# ArduinoProMicroKame.net
KiCad netlist of a schematic drawn in EAGLE
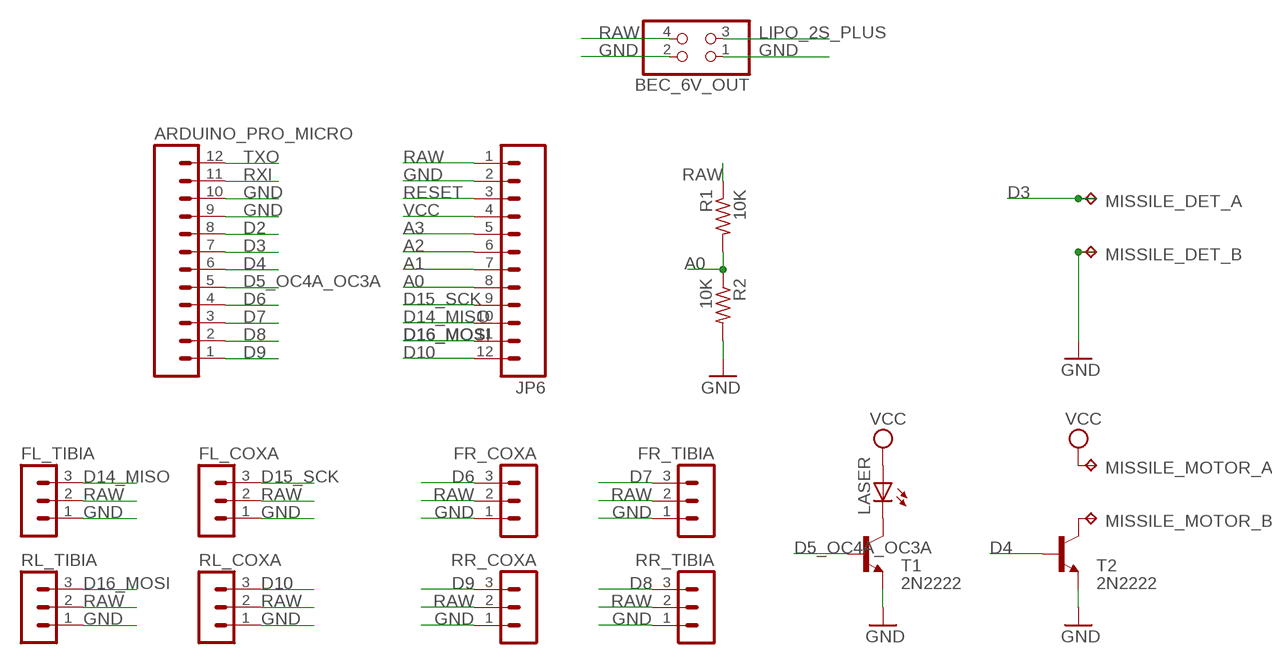
[diagram p0: schematic, sheet 1]

(export (version "E")
  (design (tool "Eeschema 10.0.6"))
  (components
    (comp (ref "ARDUINO_PRO_MICRO")
      (value "M12PTH")
      (footprint "eagle-import:1X12")
      (libsource (lib "eagle-import") (part "M12PTH"))
    )
    (comp (ref "BEC_6V_OUT")
      (value "PINHD-2X2")
      (footprint "eagle-import:2X02")
      (libsource (lib "eagle-import") (part "PINHD-2X2"))
    )
    (comp (ref "FL_COXA")
      (value "MA03-1")
      (footprint "eagle-import:MA03-1")
      (libsource (lib "eagle-import") (part "MA03-1"))
    )
    (comp (ref "FL_TIBIA")
      (value "MA03-1")
      (footprint "eagle-import:MA03-1")
      (libsource (lib "eagle-import") (part "MA03-1"))
    )
    (comp (ref "FR_COXA")
      (value "MA03-1")
      (footprint "eagle-import:MA03-1")
      (libsource (lib "eagle-import") (part "MA03-1"))
    )
    (comp (ref "FR_TIBIA")
      (value "MA03-1")
      (footprint "eagle-import:MA03-1")
      (libsource (lib "eagle-import") (part "MA03-1"))
    )
    (comp (ref "JP6")
      (value "M12PTH")
      (footprint "eagle-import:1X12")
      (libsource (lib "eagle-import") (part "M12PTH"))
    )
    (comp (ref "LASER")
      (value "LED")
      (footprint "eagle-import:SMARTLED-TTW")
      (libsource (lib "eagle-import") (part "LED"))
    )
    (comp (ref "MISSILE_DET_")
      (value "TP2P2-38-20")
      (footprint "eagle-import:P2-38-20")
      (libsource (lib "eagle-import") (part "TP2P2-38-20"))
    )
    (comp (ref "MISSILE_MOTOR_")
      (value "TP2P2-38-20")
      (footprint "eagle-import:P2-38-20")
      (libsource (lib "eagle-import") (part "TP2P2-38-20"))
    )
    (comp (ref "R1")
      (value "10K")
      (footprint "eagle-import:R2010")
      (libsource (lib "eagle-import") (part "R-US_R2010"))
    )
    (comp (ref "R2")
      (value "10K")
      (footprint "eagle-import:R2010")
      (libsource (lib "eagle-import") (part "R-US_R2010"))
    )
    (comp (ref "RL_COXA")
      (value "MA03-1")
      (footprint "eagle-import:MA03-1")
      (libsource (lib "eagle-import") (part "MA03-1"))
    )
    (comp (ref "RL_TIBIA")
      (value "MA03-1")
      (footprint "eagle-import:MA03-1")
      (libsource (lib "eagle-import") (part "MA03-1"))
    )
    (comp (ref "RR_COXA")
      (value "MA03-1")
      (footprint "eagle-import:MA03-1")
      (libsource (lib "eagle-import") (part "MA03-1"))
    )
    (comp (ref "RR_TIBIA")
      (value "MA03-1")
      (footprint "eagle-import:MA03-1")
      (libsource (lib "eagle-import") (part "MA03-1"))
    )
    (comp (ref "T1")
      (value "2N2222")
      (footprint "eagle-import:TO18")
      (libsource (lib "eagle-import") (part "2N2222"))
    )
    (comp (ref "T2")
      (value "2N2222")
      (footprint "eagle-import:TO18")
      (libsource (lib "eagle-import") (part "2N2222"))
    )
  )
  (nets
    (net (code "1") (name "/A0") (class "Default")
      (node (ref "JP6") (pin "8") (pinfunction "8_8") (pintype "passive"))
      (node (ref "R1") (pin "2") (pinfunction "2_2") (pintype "passive"))
      (node (ref "R2") (pin "1") (pinfunction "1_1") (pintype "passive"))
    )
    (net (code "2") (name "/A1") (class "Default")
      (node (ref "JP6") (pin "7") (pinfunction "7_7") (pintype "passive"))
    )
    (net (code "3") (name "/A2") (class "Default")
      (node (ref "JP6") (pin "6") (pinfunction "6_6") (pintype "passive"))
    )
    (net (code "4") (name "/A3") (class "Default")
      (node (ref "JP6") (pin "5") (pinfunction "5_5") (pintype "passive"))
    )
    (net (code "5") (name "/D2") (class "Default")
      (node (ref "ARDUINO_PRO_MICRO") (pin "8") (pinfunction "8_8") (pintype "passive"))
    )
    (net (code "6") (name "/D3") (class "Default")
      (node (ref "ARDUINO_PRO_MICRO") (pin "7") (pinfunction "7_7") (pintype "passive"))
      (node (ref "MISSILE_DET_") (pin "TP-1") (pinfunction "TP_TP-1") (pintype "input"))
    )
    (net (code "7") (name "/D4") (class "Default")
      (node (ref "ARDUINO_PRO_MICRO") (pin "6") (pinfunction "6_6") (pintype "passive"))
      (node (ref "T2") (pin "2") (pinfunction "B_2") (pintype "passive"))
    )
    (net (code "8") (name "/D5_OC4A_OC3A") (class "Default")
      (node (ref "ARDUINO_PRO_MICRO") (pin "5") (pinfunction "5_5") (pintype "passive"))
      (node (ref "T1") (pin "2") (pinfunction "B_2") (pintype "passive"))
    )
    (net (code "9") (name "/D6") (class "Default")
      (node (ref "ARDUINO_PRO_MICRO") (pin "4") (pinfunction "4_4") (pintype "passive"))
      (node (ref "FR_COXA") (pin "3") (pinfunction "3_3") (pintype "passive"))
    )
    (net (code "10") (name "/D7") (class "Default")
      (node (ref "ARDUINO_PRO_MICRO") (pin "3") (pinfunction "3_3") (pintype "passive"))
      (node (ref "FR_TIBIA") (pin "3") (pinfunction "3_3") (pintype "passive"))
    )
    (net (code "11") (name "/D8") (class "Default")
      (node (ref "ARDUINO_PRO_MICRO") (pin "2") (pinfunction "2_2") (pintype "passive"))
      (node (ref "RR_TIBIA") (pin "3") (pinfunction "3_3") (pintype "passive"))
    )
    (net (code "12") (name "/D9") (class "Default")
      (node (ref "ARDUINO_PRO_MICRO") (pin "1") (pinfunction "1_1") (pintype "passive"))
      (node (ref "RR_COXA") (pin "3") (pinfunction "3_3") (pintype "passive"))
    )
    (net (code "13") (name "/D10") (class "Default")
      (node (ref "JP6") (pin "12") (pinfunction "12_12") (pintype "passive"))
      (node (ref "RL_COXA") (pin "3") (pinfunction "3_3") (pintype "passive"))
    )
    (net (code "14") (name "/D14_MISO") (class "Default")
      (node (ref "FL_TIBIA") (pin "3") (pinfunction "3_3") (pintype "passive"))
      (node (ref "JP6") (pin "10") (pinfunction "10_10") (pintype "passive"))
    )
    (net (code "15") (name "/D15_SCK") (class "Default")
      (node (ref "FL_COXA") (pin "3") (pinfunction "3_3") (pintype "passive"))
      (node (ref "JP6") (pin "9") (pinfunction "9_9") (pintype "passive"))
    )
    (net (code "16") (name "/D16_MOSI") (class "Default")
      (node (ref "JP6") (pin "11") (pinfunction "11_11") (pintype "passive"))
      (node (ref "RL_TIBIA") (pin "3") (pinfunction "3_3") (pintype "passive"))
    )
    (net (code "17") (name "/LIPO_2S_PLUS") (class "Default")
      (node (ref "BEC_6V_OUT") (pin "3") (pinfunction "3_3") (pintype "passive"))
    )
    (net (code "18") (name "/RAW") (class "Default")
      (node (ref "BEC_6V_OUT") (pin "4") (pinfunction "4_4") (pintype "passive"))
      (node (ref "FL_COXA") (pin "2") (pinfunction "2_2") (pintype "passive"))
      (node (ref "FL_TIBIA") (pin "2") (pinfunction "2_2") (pintype "passive"))
      (node (ref "FR_COXA") (pin "2") (pinfunction "2_2") (pintype "passive"))
      (node (ref "FR_TIBIA") (pin "2") (pinfunction "2_2") (pintype "passive"))
      (node (ref "JP6") (pin "1") (pinfunction "1_1") (pintype "passive"))
      (node (ref "R1") (pin "1") (pinfunction "1_1") (pintype "passive"))
      (node (ref "RL_COXA") (pin "2") (pinfunction "2_2") (pintype "passive"))
      (node (ref "RL_TIBIA") (pin "2") (pinfunction "2_2") (pintype "passive"))
      (node (ref "RR_COXA") (pin "2") (pinfunction "2_2") (pintype "passive"))
      (node (ref "RR_TIBIA") (pin "2") (pinfunction "2_2") (pintype "passive"))
    )
    (net (code "19") (name "/RESET") (class "Default")
      (node (ref "JP6") (pin "3") (pinfunction "3_3") (pintype "passive"))
    )
    (net (code "20") (name "/RXI") (class "Default")
      (node (ref "ARDUINO_PRO_MICRO") (pin "11") (pinfunction "11_11") (pintype "passive"))
    )
    (net (code "21") (name "/TXO") (class "Default")
      (node (ref "ARDUINO_PRO_MICRO") (pin "12") (pinfunction "12_12") (pintype "passive"))
    )
    (net (code "22") (name "GND") (class "Default")
      (node (ref "ARDUINO_PRO_MICRO") (pin "10") (pinfunction "10_10") (pintype "passive"))
      (node (ref "ARDUINO_PRO_MICRO") (pin "9") (pinfunction "9_9") (pintype "passive"))
      (node (ref "BEC_6V_OUT") (pin "1") (pinfunction "1_1") (pintype "passive"))
      (node (ref "BEC_6V_OUT") (pin "2") (pinfunction "2_2") (pintype "passive"))
      (node (ref "FL_COXA") (pin "1") (pinfunction "1_1") (pintype "passive"))
      (node (ref "FL_TIBIA") (pin "1") (pinfunction "1_1") (pintype "passive"))
      (node (ref "FR_COXA") (pin "1") (pinfunction "1_1") (pintype "passive"))
      (node (ref "FR_TIBIA") (pin "1") (pinfunction "1_1") (pintype "passive"))
      (node (ref "JP6") (pin "2") (pinfunction "2_2") (pintype "passive"))
      (node (ref "MISSILE_DET_") (pin "TP-2") (pinfunction "TP_TP-2") (pintype "input"))
      (node (ref "R2") (pin "2") (pinfunction "2_2") (pintype "passive"))
      (node (ref "RL_COXA") (pin "1") (pinfunction "1_1") (pintype "passive"))
      (node (ref "RL_TIBIA") (pin "1") (pinfunction "1_1") (pintype "passive"))
      (node (ref "RR_COXA") (pin "1") (pinfunction "1_1") (pintype "passive"))
      (node (ref "RR_TIBIA") (pin "1") (pinfunction "1_1") (pintype "passive"))
      (node (ref "T1") (pin "1") (pinfunction "E_1") (pintype "passive"))
      (node (ref "T2") (pin "1") (pinfunction "E_1") (pintype "passive"))
    )
    (net (code "23") (name "Net-(LASER-C)") (class "Default")
      (node (ref "LASER") (pin "C@1") (pinfunction "C_C@1") (pintype "passive"))
      (node (ref "T1") (pin "3") (pinfunction "C_3") (pintype "passive"))
    )
    (net (code "24") (name "Net-(MISSILE_MOTOR_B-TP)") (class "Default")
      (node (ref "MISSILE_MOTOR_") (pin "TP-2") (pinfunction "TP_TP-2") (pintype "input"))
      (node (ref "T2") (pin "3") (pinfunction "C_3") (pintype "passive"))
    )
    (net (code "25") (name "VCC") (class "Default")
      (node (ref "JP6") (pin "4") (pinfunction "4_4") (pintype "passive"))
      (node (ref "LASER") (pin "A@1") (pinfunction "A_A@1") (pintype "passive"))
      (node (ref "MISSILE_MOTOR_") (pin "TP-1") (pinfunction "TP_TP-1") (pintype "input"))
    )
  )
)
